# NE555_BlinkPCB.net
KiCad netlist of a schematic drawn in EasyEDA Pro
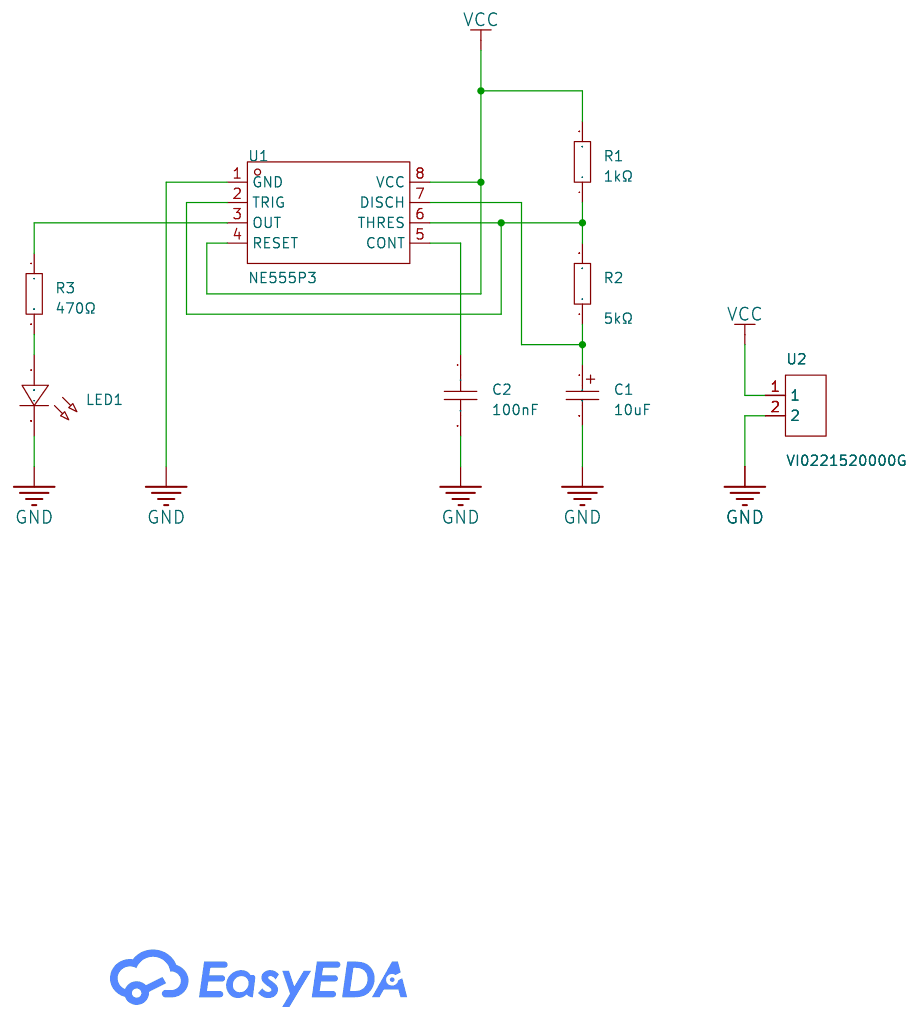
[diagram p0: schematic sheet]

(export (version "E")
  (design (tool "Eeschema 10.0.6"))
  (components
    (comp (ref "C1")
      (value "10uF")
      (footprint "easyedapro:CAP-SMD_BD3.0-L3.3-W3.3-RD")
      (fields
        (field (name "Manufacturer Part") "KM106M016D11RR0VH2FP0")
        (field (name "Manufacturer") "Chengx(承兴)")
      )
      (libsource (lib "easyedapro") (part "C_Ele_SMD"))
    )
    (comp (ref "C2")
      (value "100nF")
      (footprint "easyedapro:C0201")
      (fields
        (field (name "Manufacturer Part") "CC1H104MC1FD3F6C10SA")
        (field (name "Manufacturer") "Dersonic(德尔创)")
      )
      (libsource (lib "easyedapro") (part "CAP"))
    )
    (comp (ref "LED1")
      (value "~")
      (footprint "easyedapro:LED-TH_BD5.8-P2.54-FD")
      (libsource (lib "easyedapro") (part "LED_TH-R"))
    )
    (comp (ref "R1")
      (value "1kΩ")
      (footprint "easyedapro:RES-TH_BD1.8-L3.2-P7.20-D0.4")
      (libsource (lib "easyedapro") (part "Res"))
    )
    (comp (ref "R2")
      (value "5kΩ")
      (footprint "easyedapro:RES-TH_BD1.8-L3.2-P7.20-D0.4")
      (libsource (lib "easyedapro") (part "Res"))
    )
    (comp (ref "R3")
      (value "470Ω")
      (footprint "easyedapro:RES-TH_BD1.8-L3.2-P7.20-D0.4")
      (libsource (lib "easyedapro") (part "Res"))
    )
    (comp (ref "U1")
      (value "NE555P3")
      (footprint "easyedapro:PDIP-8_L9.6-W6.4-P2.54-LS7.9-BL-1")
      (fields (field (name "Manufacturer") "TI(德州仪器)"))
      (libsource (lib "easyedapro") (part "NE555P3"))
    )
    (comp (ref "U2")
      (value "VI0221520000G")
      (footprint "easyedapro:CONN-TH_2P-P3.96_DB301V-3.96-2P-GN-S")
      (fields (field (name "Manufacturer") "Amphenol"))
      (libsource (lib "easyedapro") (part "DB301V-3.96-2P-GN-S"))
    )
  )
  (nets
    (net (code "1") (name "GND") (class "Default")
      (node (ref "C1") (pin "2") (pinfunction "2_2") (pintype "input"))
      (node (ref "C2") (pin "2") (pinfunction "2_2") (pintype "input"))
      (node (ref "LED1") (pin "2") (pinfunction "A_2") (pintype "input"))
      (node (ref "U1") (pin "1") (pinfunction "GND_1") (pintype "unspecified"))
      (node (ref "U2") (pin "2") (pinfunction "2_2") (pintype "unspecified"))
    )
    (net (code "2") (name "Net-(LED1-C)") (class "Default")
      (node (ref "LED1") (pin "1") (pinfunction "C_1") (pintype "input"))
      (node (ref "R3") (pin "2") (pinfunction "2_2") (pintype "input"))
    )
    (net (code "3") (name "Net-(U1-CONT)") (class "Default")
      (node (ref "C2") (pin "1") (pinfunction "1_1") (pintype "input"))
      (node (ref "U1") (pin "5") (pinfunction "CONT_5") (pintype "unspecified"))
    )
    (net (code "4") (name "Net-(U1-DISCH)") (class "Default")
      (node (ref "C1") (pin "1") (pinfunction "1_1") (pintype "input"))
      (node (ref "R2") (pin "1") (pinfunction "1_1") (pintype "input"))
      (node (ref "U1") (pin "7") (pinfunction "DISCH_7") (pintype "unspecified"))
    )
    (net (code "5") (name "Net-(U1-OUT)") (class "Default")
      (node (ref "R3") (pin "1") (pinfunction "1_1") (pintype "input"))
      (node (ref "U1") (pin "3") (pinfunction "OUT_3") (pintype "unspecified"))
    )
    (net (code "6") (name "Net-(U1-THRES)") (class "Default")
      (node (ref "R1") (pin "1") (pinfunction "1_1") (pintype "input"))
      (node (ref "R2") (pin "2") (pinfunction "2_2") (pintype "input"))
      (node (ref "U1") (pin "2") (pinfunction "TRIG_2") (pintype "unspecified"))
      (node (ref "U1") (pin "6") (pinfunction "THRES_6") (pintype "unspecified"))
    )
    (net (code "7") (name "VCC") (class "Default")
      (node (ref "R1") (pin "2") (pinfunction "2_2") (pintype "input"))
      (node (ref "U1") (pin "4") (pinfunction "RESET_4") (pintype "unspecified"))
      (node (ref "U1") (pin "8") (pinfunction "VCC_8") (pintype "unspecified"))
      (node (ref "U2") (pin "1") (pinfunction "1_1") (pintype "unspecified"))
    )
  )
)
